# SCH_research_roject_2023-12-18.net
KiCad netlist of a schematic drawn in EasyEDA
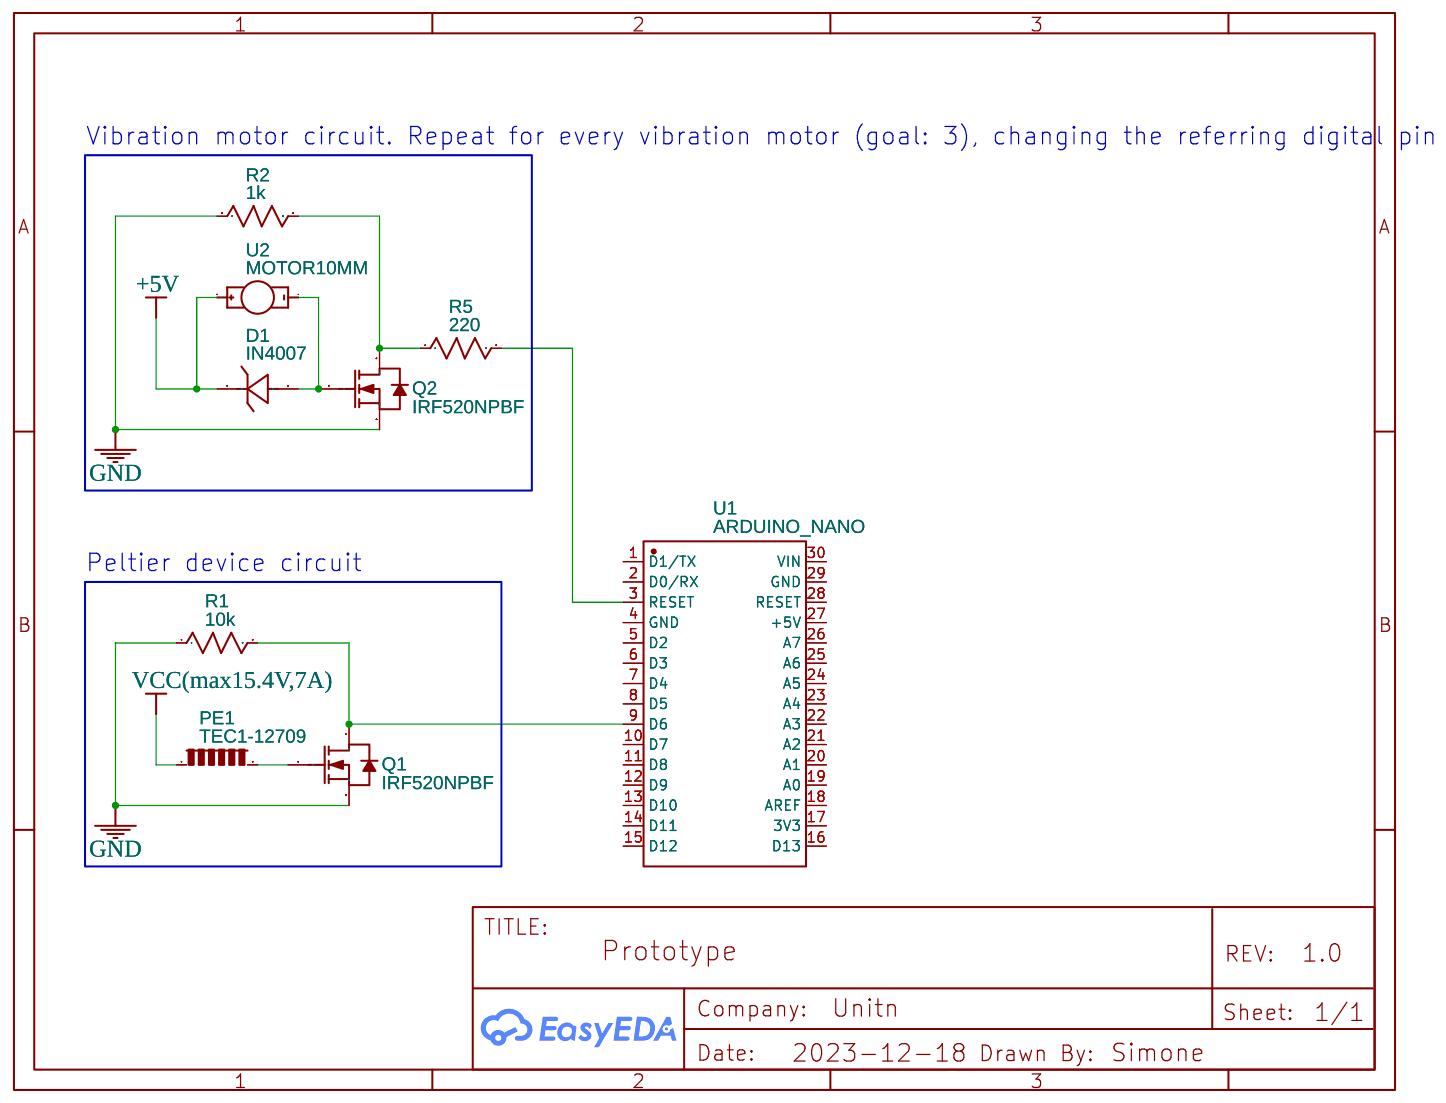
[diagram p0: schematic sheet]

(export (version "E")
  (design (tool "Eeschema 10.0.6"))
  (components
    (comp (ref "D1") (value "IN4007") (libsource (lib "") (part "IN4007")))
    (comp (ref "PE1") (value "TEC1-12709") (libsource (lib "") (part "Peltier_Element")))
    (comp (ref "Q1")
      (value "IRF520NPBF")
      (fields (field (name "Manufacturer") "Infineon(英飞凌)"))
      (libsource (lib "") (part "IRF520NPBF"))
    )
    (comp (ref "Q2")
      (value "IRF520NPBF")
      (fields (field (name "Manufacturer") "Infineon(英飞凌)"))
      (libsource (lib "") (part "IRF520NPBF"))
    )
    (comp (ref "R1") (value "10k") (libsource (lib "") (part "R_0603_US")))
    (comp (ref "R2") (value "1k") (libsource (lib "") (part "R_0603_US")))
    (comp (ref "R5") (value "220") (libsource (lib "") (part "R_0603_US")))
    (comp (ref "U1") (value "ARDUINO_NANO") (libsource (lib "") (part "ARDUINO_NANO")))
    (comp (ref "U2") (value "MOTOR10MM") (libsource (lib "") (part "MOTOR10MM")))
  )
  (nets
    (net (code "1") (name "+5V") (class "Default")
      (node (ref "D1") (pin "1") (pinfunction "C_1") (pintype "unspecified"))
      (node (ref "U2") (pin "+") (pinfunction "+_+") (pintype "unspecified"))
    )
    (net (code "2") (name "GND") (class "Default")
      (node (ref "Q1") (pin "3") (pinfunction "S_3") (pintype "unspecified"))
      (node (ref "Q2") (pin "3") (pinfunction "S_3") (pintype "unspecified"))
      (node (ref "R1") (pin "1") (pinfunction "1_1") (pintype "unspecified"))
      (node (ref "R2") (pin "1") (pinfunction "1_1") (pintype "unspecified"))
    )
    (net (code "3") (name "Net-(D1-A)") (class "Default")
      (node (ref "D1") (pin "2") (pinfunction "A_2") (pintype "unspecified"))
      (node (ref "Q2") (pin "1") (pinfunction "G_1") (pintype "unspecified"))
      (node (ref "U2") (pin "-") (pinfunction "-_-") (pintype "unspecified"))
    )
    (net (code "4") (name "Net-(Q1-D)") (class "Default")
      (node (ref "Q1") (pin "2") (pinfunction "D_2") (pintype "unspecified"))
      (node (ref "R1") (pin "2") (pinfunction "2_2") (pintype "unspecified"))
      (node (ref "U1") (pin "9") (pinfunction "D6_9") (pintype "unspecified"))
    )
    (net (code "5") (name "Net-(Q1-G)") (class "Default")
      (node (ref "PE1") (pin "2") (pintype "unspecified"))
      (node (ref "Q1") (pin "1") (pinfunction "G_1") (pintype "unspecified"))
    )
    (net (code "6") (name "Net-(Q2-D)") (class "Default")
      (node (ref "Q2") (pin "2") (pinfunction "D_2") (pintype "unspecified"))
      (node (ref "R2") (pin "2") (pinfunction "2_2") (pintype "unspecified"))
      (node (ref "R5") (pin "1") (pinfunction "1_1") (pintype "unspecified"))
    )
    (net (code "7") (name "Net-(R5-Pad2)") (class "Default")
      (node (ref "R5") (pin "2") (pinfunction "2_2") (pintype "unspecified"))
      (node (ref "U1") (pin "3") (pinfunction "RESET_3") (pintype "unspecified"))
    )
    (net (code "8") (name "VCC(max15.4V,7A)") (class "Default")
      (node (ref "PE1") (pin "1") (pintype "unspecified"))
    )
    (net (code "9") (name "unconnected-(U1-+5V-Pad27)") (class "Default")
      (node (ref "U1") (pin "27") (pinfunction "+5V_27") (pintype "unspecified"))
    )
    (net (code "10") (name "unconnected-(U1-3V3-Pad17)") (class "Default")
      (node (ref "U1") (pin "17") (pinfunction "3V3_17") (pintype "unspecified"))
    )
    (net (code "11") (name "unconnected-(U1-A0-Pad19)") (class "Default")
      (node (ref "U1") (pin "19") (pinfunction "A0_19") (pintype "unspecified"))
    )
    (net (code "12") (name "unconnected-(U1-A1-Pad20)") (class "Default")
      (node (ref "U1") (pin "20") (pinfunction "A1_20") (pintype "unspecified"))
    )
    (net (code "13") (name "unconnected-(U1-A2-Pad21)") (class "Default")
      (node (ref "U1") (pin "21") (pinfunction "A2_21") (pintype "unspecified"))
    )
    (net (code "14") (name "unconnected-(U1-A3-Pad22)") (class "Default")
      (node (ref "U1") (pin "22") (pinfunction "A3_22") (pintype "unspecified"))
    )
    (net (code "15") (name "unconnected-(U1-A4-Pad23)") (class "Default")
      (node (ref "U1") (pin "23") (pinfunction "A4_23") (pintype "unspecified"))
    )
    (net (code "16") (name "unconnected-(U1-A5-Pad24)") (class "Default")
      (node (ref "U1") (pin "24") (pinfunction "A5_24") (pintype "unspecified"))
    )
    (net (code "17") (name "unconnected-(U1-A6-Pad25)") (class "Default")
      (node (ref "U1") (pin "25") (pinfunction "A6_25") (pintype "unspecified"))
    )
    (net (code "18") (name "unconnected-(U1-A7-Pad26)") (class "Default")
      (node (ref "U1") (pin "26") (pinfunction "A7_26") (pintype "unspecified"))
    )
    (net (code "19") (name "unconnected-(U1-AREF-Pad18)") (class "Default")
      (node (ref "U1") (pin "18") (pinfunction "AREF_18") (pintype "unspecified"))
    )
    (net (code "20") (name "unconnected-(U1-D0{slash}RX-Pad2)") (class "Default")
      (node (ref "U1") (pin "2") (pinfunction "D0/RX_2") (pintype "unspecified"))
    )
    (net (code "21") (name "unconnected-(U1-D1{slash}TX-Pad1)") (class "Default")
      (node (ref "U1") (pin "1") (pinfunction "D1/TX_1") (pintype "unspecified"))
    )
    (net (code "22") (name "unconnected-(U1-D2-Pad5)") (class "Default")
      (node (ref "U1") (pin "5") (pinfunction "D2_5") (pintype "unspecified"))
    )
    (net (code "23") (name "unconnected-(U1-D3-Pad6)") (class "Default")
      (node (ref "U1") (pin "6") (pinfunction "D3_6") (pintype "unspecified"))
    )
    (net (code "24") (name "unconnected-(U1-D4-Pad7)") (class "Default")
      (node (ref "U1") (pin "7") (pinfunction "D4_7") (pintype "unspecified"))
    )
    (net (code "25") (name "unconnected-(U1-D5-Pad8)") (class "Default")
      (node (ref "U1") (pin "8") (pinfunction "D5_8") (pintype "unspecified"))
    )
    (net (code "26") (name "unconnected-(U1-D7-Pad10)") (class "Default")
      (node (ref "U1") (pin "10") (pinfunction "D7_10") (pintype "unspecified"))
    )
    (net (code "27") (name "unconnected-(U1-D8-Pad11)") (class "Default")
      (node (ref "U1") (pin "11") (pinfunction "D8_11") (pintype "unspecified"))
    )
    (net (code "28") (name "unconnected-(U1-D9-Pad12)") (class "Default")
      (node (ref "U1") (pin "12") (pinfunction "D9_12") (pintype "unspecified"))
    )
    (net (code "29") (name "unconnected-(U1-D10-Pad13)") (class "Default")
      (node (ref "U1") (pin "13") (pinfunction "D10_13") (pintype "unspecified"))
    )
    (net (code "30") (name "unconnected-(U1-D11-Pad14)") (class "Default")
      (node (ref "U1") (pin "14") (pinfunction "D11_14") (pintype "unspecified"))
    )
    (net (code "31") (name "unconnected-(U1-D12-Pad15)") (class "Default")
      (node (ref "U1") (pin "15") (pinfunction "D12_15") (pintype "unspecified"))
    )
    (net (code "32") (name "unconnected-(U1-D13-Pad16)") (class "Default")
      (node (ref "U1") (pin "16") (pinfunction "D13_16") (pintype "unspecified"))
    )
    (net (code "33") (name "unconnected-(U1-GND-Pad4)") (class "Default")
      (node (ref "U1") (pin "4") (pinfunction "GND_4") (pintype "unspecified"))
    )
    (net (code "34") (name "unconnected-(U1-GND-Pad29)") (class "Default")
      (node (ref "U1") (pin "29") (pinfunction "GND_29") (pintype "unspecified"))
    )
    (net (code "35") (name "unconnected-(U1-RESET-Pad28)") (class "Default")
      (node (ref "U1") (pin "28") (pinfunction "RESET_28") (pintype "unspecified"))
    )
    (net (code "36") (name "unconnected-(U1-VIN-Pad30)") (class "Default")
      (node (ref "U1") (pin "30") (pinfunction "VIN_30") (pintype "unspecified"))
    )
  )
)
